# Filters_3.net
KiCad netlist of a schematic drawn in Altium Designer
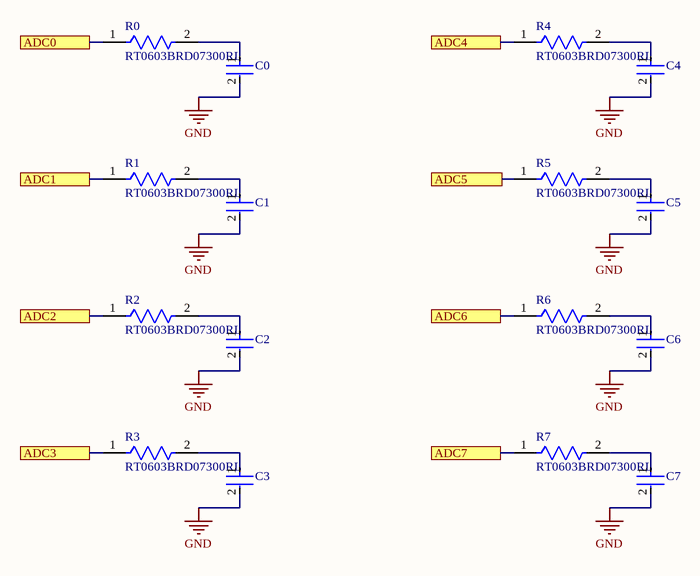
[diagram p0: Filters.3.SchDoc]

(export (version "E")
  (design (tool "Eeschema 10.0.6"))
  (components
    (comp (ref "C0")
      (value "C0603C104M4RAC")
      (footprint "FP-C0603C-CF-MFG")
      (description "C0603 0.10 μF X7R 30ppm/°C 20.00% 16 V")
      (fields
        (field (name "OCTOPART") "https://octopart.com/c0603c104m4rac-kemet-1325405")
        (field (name "TOLERANCE") "0.2")
      )
      (libsource (lib "Altium Content Vault") (part "b4654b650e69147ec39a6b967a45e02"))
    )
    (comp (ref "C1")
      (value "C0603C104M4RAC")
      (footprint "FP-C0603C-CF-MFG")
      (description "C0603 0.10 μF X7R 30ppm/°C 20.00% 16 V")
      (fields
        (field (name "OCTOPART") "https://octopart.com/c0603c104m4rac-kemet-1325405")
        (field (name "TOLERANCE") "0.2")
      )
      (libsource (lib "Altium Content Vault") (part "b4654b650e69147ec39a6b967a45e02"))
    )
    (comp (ref "C2")
      (value "C0603C104M4RAC")
      (footprint "FP-C0603C-CF-MFG")
      (description "C0603 0.10 μF X7R 30ppm/°C 20.00% 16 V")
      (fields
        (field (name "OCTOPART") "https://octopart.com/c0603c104m4rac-kemet-1325405")
        (field (name "TOLERANCE") "0.2")
      )
      (libsource (lib "Altium Content Vault") (part "b4654b650e69147ec39a6b967a45e02"))
    )
    (comp (ref "C3")
      (value "C0603C104M4RAC")
      (footprint "FP-C0603C-CF-MFG")
      (description "C0603 0.10 μF X7R 30ppm/°C 20.00% 16 V")
      (fields
        (field (name "OCTOPART") "https://octopart.com/c0603c104m4rac-kemet-1325405")
        (field (name "TOLERANCE") "0.2")
      )
      (libsource (lib "Altium Content Vault") (part "b4654b650e69147ec39a6b967a45e02"))
    )
    (comp (ref "C4")
      (value "C0603C104M4RAC")
      (footprint "FP-C0603C-CF-MFG")
      (description "C0603 0.10 μF X7R 30ppm/°C 20.00% 16 V")
      (fields
        (field (name "OCTOPART") "https://octopart.com/c0603c104m4rac-kemet-1325405")
        (field (name "TOLERANCE") "0.2")
      )
      (libsource (lib "Altium Content Vault") (part "b4654b650e69147ec39a6b967a45e02"))
    )
    (comp (ref "C5")
      (value "C0603C104M4RAC")
      (footprint "FP-C0603C-CF-MFG")
      (description "C0603 0.10 μF X7R 30ppm/°C 20.00% 16 V")
      (fields
        (field (name "OCTOPART") "https://octopart.com/c0603c104m4rac-kemet-1325405")
        (field (name "TOLERANCE") "0.2")
      )
      (libsource (lib "Altium Content Vault") (part "b4654b650e69147ec39a6b967a45e02"))
    )
    (comp (ref "C6")
      (value "C0603C104M4RAC")
      (footprint "FP-C0603C-CF-MFG")
      (description "C0603 0.10 μF X7R 30ppm/°C 20.00% 16 V")
      (fields
        (field (name "OCTOPART") "https://octopart.com/c0603c104m4rac-kemet-1325405")
        (field (name "TOLERANCE") "0.2")
      )
      (libsource (lib "Altium Content Vault") (part "b4654b650e69147ec39a6b967a45e02"))
    )
    (comp (ref "C7")
      (value "C0603C104M4RAC")
      (footprint "FP-C0603C-CF-MFG")
      (description "C0603 0.10 μF X7R 30ppm/°C 20.00% 16 V")
      (fields
        (field (name "OCTOPART") "https://octopart.com/c0603c104m4rac-kemet-1325405")
        (field (name "TOLERANCE") "0.2")
      )
      (libsource (lib "Altium Content Vault") (part "b4654b650e69147ec39a6b967a45e02"))
    )
    (comp (ref "R0")
      (value "RT0603BRD07300RL")
      (footprint "FP-RT0603-MFG")
      (description "RES SMD 300 OHM 0.1% 1/10W 0603")
      (fields (field (name "MANUFACTURER") "Yageo") (field (name "TOLERANCE") "0.001"))
      (libsource (lib "Altium Content Vault") (part "1029c3af85768c4190bb7ad29bc67b5"))
    )
    (comp (ref "R1")
      (value "RT0603BRD07300RL")
      (footprint "FP-RT0603-MFG")
      (description "RES SMD 300 OHM 0.1% 1/10W 0603")
      (fields (field (name "MANUFACTURER") "Yageo") (field (name "TOLERANCE") "0.001"))
      (libsource (lib "Altium Content Vault") (part "1029c3af85768c4190bb7ad29bc67b5"))
    )
    (comp (ref "R2")
      (value "RT0603BRD07300RL")
      (footprint "FP-RT0603-MFG")
      (description "RES SMD 300 OHM 0.1% 1/10W 0603")
      (fields (field (name "MANUFACTURER") "Yageo") (field (name "TOLERANCE") "0.001"))
      (libsource (lib "Altium Content Vault") (part "1029c3af85768c4190bb7ad29bc67b5"))
    )
    (comp (ref "R3")
      (value "RT0603BRD07300RL")
      (footprint "FP-RT0603-MFG")
      (description "RES SMD 300 OHM 0.1% 1/10W 0603")
      (fields (field (name "MANUFACTURER") "Yageo") (field (name "TOLERANCE") "0.001"))
      (libsource (lib "Altium Content Vault") (part "1029c3af85768c4190bb7ad29bc67b5"))
    )
    (comp (ref "R4")
      (value "RT0603BRD07300RL")
      (footprint "FP-RT0603-MFG")
      (description "RES SMD 300 OHM 0.1% 1/10W 0603")
      (fields (field (name "MANUFACTURER") "Yageo") (field (name "TOLERANCE") "0.001"))
      (libsource (lib "Altium Content Vault") (part "1029c3af85768c4190bb7ad29bc67b5"))
    )
    (comp (ref "R5")
      (value "RT0603BRD07300RL")
      (footprint "FP-RT0603-MFG")
      (description "RES SMD 300 OHM 0.1% 1/10W 0603")
      (fields (field (name "MANUFACTURER") "Yageo") (field (name "TOLERANCE") "0.001"))
      (libsource (lib "Altium Content Vault") (part "1029c3af85768c4190bb7ad29bc67b5"))
    )
    (comp (ref "R6")
      (value "RT0603BRD07300RL")
      (footprint "FP-RT0603-MFG")
      (description "RES SMD 300 OHM 0.1% 1/10W 0603")
      (fields (field (name "MANUFACTURER") "Yageo") (field (name "TOLERANCE") "0.001"))
      (libsource (lib "Altium Content Vault") (part "1029c3af85768c4190bb7ad29bc67b5"))
    )
    (comp (ref "R7")
      (value "RT0603BRD07300RL")
      (footprint "FP-RT0603-MFG")
      (description "RES SMD 300 OHM 0.1% 1/10W 0603")
      (fields (field (name "MANUFACTURER") "Yageo") (field (name "TOLERANCE") "0.001"))
      (libsource (lib "Altium Content Vault") (part "1029c3af85768c4190bb7ad29bc67b5"))
    )
  )
  (nets
    (net (code "1") (name "/ADC0") (class "Default")
      (node (ref "R0") (pin "1") (pinfunction "1_1") (pintype "passive"))
    )
    (net (code "2") (name "/ADC1") (class "Default")
      (node (ref "R1") (pin "1") (pinfunction "1_1") (pintype "passive"))
    )
    (net (code "3") (name "/ADC2") (class "Default")
      (node (ref "R2") (pin "1") (pinfunction "1_1") (pintype "passive"))
    )
    (net (code "4") (name "/ADC3") (class "Default")
      (node (ref "R3") (pin "1") (pinfunction "1_1") (pintype "passive"))
    )
    (net (code "5") (name "/ADC4") (class "Default")
      (node (ref "R4") (pin "1") (pinfunction "1_1") (pintype "passive"))
    )
    (net (code "6") (name "/ADC5") (class "Default")
      (node (ref "R5") (pin "1") (pinfunction "1_1") (pintype "passive"))
    )
    (net (code "7") (name "/ADC6") (class "Default")
      (node (ref "R6") (pin "1") (pinfunction "1_1") (pintype "passive"))
    )
    (net (code "8") (name "/ADC7") (class "Default")
      (node (ref "R7") (pin "1") (pinfunction "1_1") (pintype "passive"))
    )
    (net (code "9") (name "GND") (class "Default")
      (node (ref "C0") (pin "2") (pinfunction "2_2") (pintype "passive"))
      (node (ref "C1") (pin "2") (pinfunction "2_2") (pintype "passive"))
      (node (ref "C2") (pin "2") (pinfunction "2_2") (pintype "passive"))
      (node (ref "C3") (pin "2") (pinfunction "2_2") (pintype "passive"))
      (node (ref "C4") (pin "2") (pinfunction "2_2") (pintype "passive"))
      (node (ref "C5") (pin "2") (pinfunction "2_2") (pintype "passive"))
      (node (ref "C6") (pin "2") (pinfunction "2_2") (pintype "passive"))
      (node (ref "C7") (pin "2") (pinfunction "2_2") (pintype "passive"))
    )
    (net (code "10") (name "Net-(C0-Pad1)") (class "Default")
      (node (ref "C0") (pin "1") (pinfunction "1_1") (pintype "passive"))
      (node (ref "R0") (pin "2") (pinfunction "2_2") (pintype "passive"))
    )
    (net (code "11") (name "Net-(C1-Pad1)") (class "Default")
      (node (ref "C1") (pin "1") (pinfunction "1_1") (pintype "passive"))
      (node (ref "R1") (pin "2") (pinfunction "2_2") (pintype "passive"))
    )
    (net (code "12") (name "Net-(C2-Pad1)") (class "Default")
      (node (ref "C2") (pin "1") (pinfunction "1_1") (pintype "passive"))
      (node (ref "R2") (pin "2") (pinfunction "2_2") (pintype "passive"))
    )
    (net (code "13") (name "Net-(C3-Pad1)") (class "Default")
      (node (ref "C3") (pin "1") (pinfunction "1_1") (pintype "passive"))
      (node (ref "R3") (pin "2") (pinfunction "2_2") (pintype "passive"))
    )
    (net (code "14") (name "Net-(C4-Pad1)") (class "Default")
      (node (ref "C4") (pin "1") (pinfunction "1_1") (pintype "passive"))
      (node (ref "R4") (pin "2") (pinfunction "2_2") (pintype "passive"))
    )
    (net (code "15") (name "Net-(C5-Pad1)") (class "Default")
      (node (ref "C5") (pin "1") (pinfunction "1_1") (pintype "passive"))
      (node (ref "R5") (pin "2") (pinfunction "2_2") (pintype "passive"))
    )
    (net (code "16") (name "Net-(C6-Pad1)") (class "Default")
      (node (ref "C6") (pin "1") (pinfunction "1_1") (pintype "passive"))
      (node (ref "R6") (pin "2") (pinfunction "2_2") (pintype "passive"))
    )
    (net (code "17") (name "Net-(C7-Pad1)") (class "Default")
      (node (ref "C7") (pin "1") (pinfunction "1_1") (pintype "passive"))
      (node (ref "R7") (pin "2") (pinfunction "2_2") (pintype "passive"))
    )
  )
)
